# Sensor.net
KiCad netlist of a schematic drawn in Altium Designer
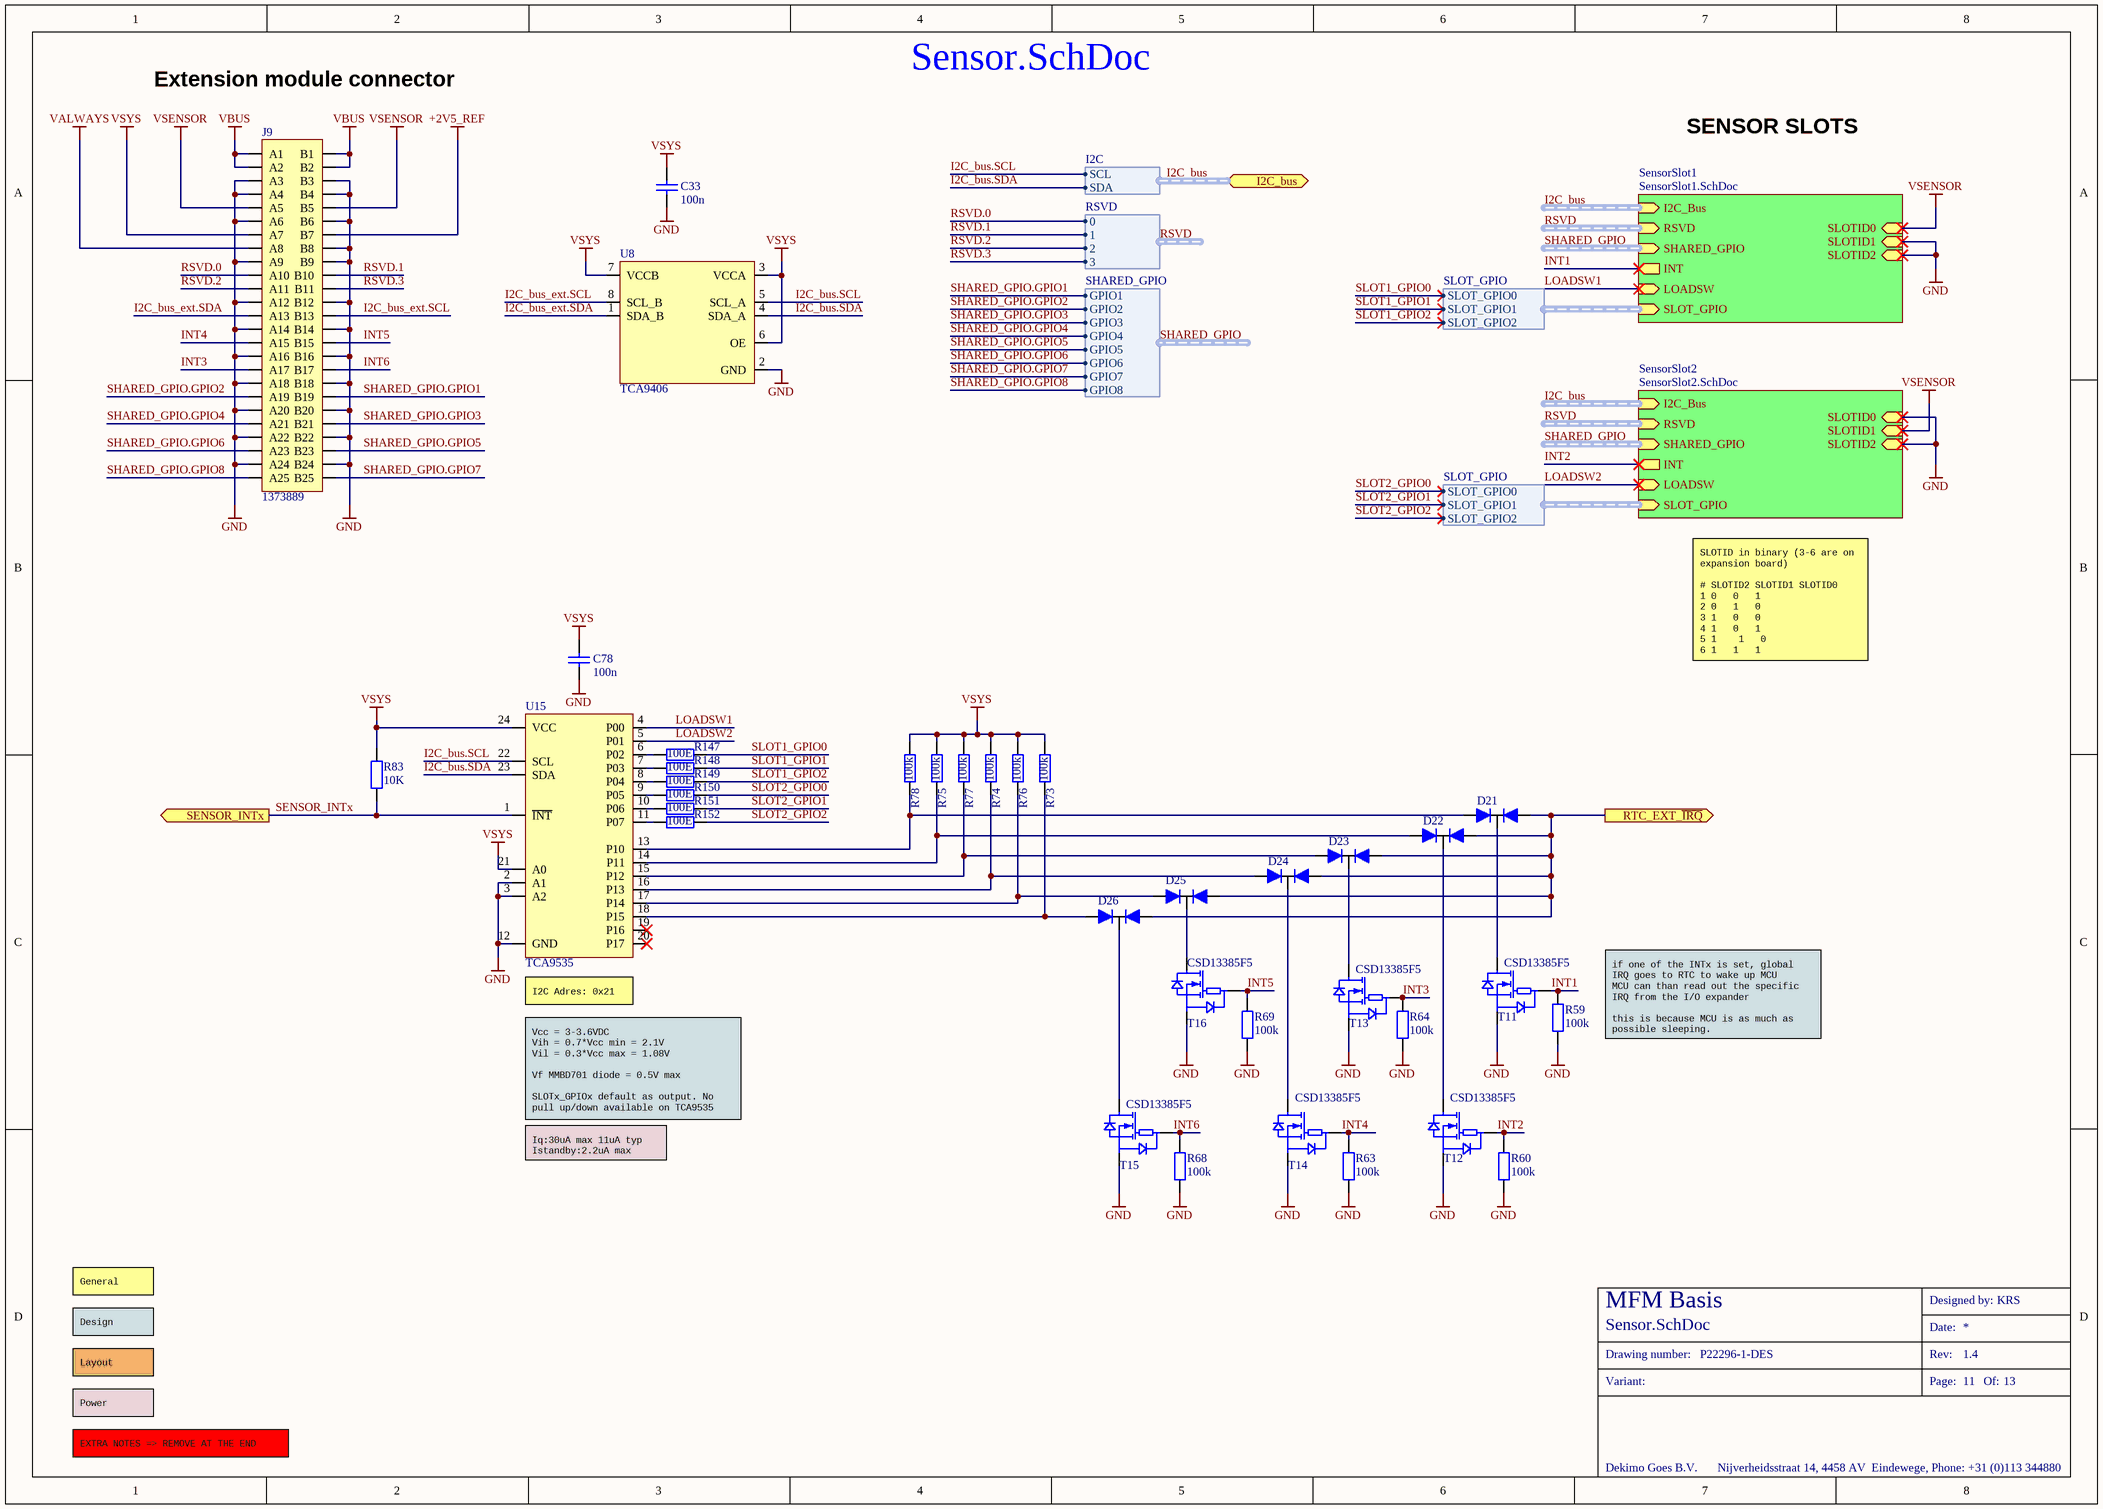
[diagram p0: Sensor.SchDoc]

(export (version "E")
  (design (tool "Eeschema 10.0.6"))
  (components
    (comp (ref "C33")
      (value "100n")
      (footprint "CAPC1608X09N")
      (description "100nF 50V 10% X7R")
      (libsource (lib "DCI") (part "Capacitor_NP"))
    )
    (comp (ref "C78")
      (value "100n")
      (footprint "CAPC1608X09N")
      (description "100nF 50V 10% X7R")
      (libsource (lib "DCI") (part "Capacitor_NP"))
    )
    (comp (ref "D21")
      (value "DIO RB508FM-40C")
      (footprint "SOT-650G001-003")
      (description "RB508, 40V, 80mA 2 com cat dio")
      (libsource (lib "DCI") (part "Diode_CC"))
    )
    (comp (ref "D22")
      (value "DIO RB508FM-40C")
      (footprint "SOT-650G001-003")
      (description "RB508, 40V, 80mA 2 com cat dio")
      (libsource (lib "DCI") (part "Diode_CC"))
    )
    (comp (ref "D23")
      (value "DIO RB508FM-40C")
      (footprint "SOT-650G001-003")
      (description "RB508, 40V, 80mA 2 com cat dio")
      (libsource (lib "DCI") (part "Diode_CC"))
    )
    (comp (ref "D24")
      (value "DIO RB508FM-40C")
      (footprint "SOT-650G001-003")
      (description "RB508, 40V, 80mA 2 com cat dio")
      (libsource (lib "DCI") (part "Diode_CC"))
    )
    (comp (ref "D25")
      (value "DIO RB508FM-40C")
      (footprint "SOT-650G001-003")
      (description "RB508, 40V, 80mA 2 com cat dio")
      (libsource (lib "DCI") (part "Diode_CC"))
    )
    (comp (ref "D26")
      (value "DIO RB508FM-40C")
      (footprint "SOT-650G001-003")
      (description "RB508, 40V, 80mA 2 com cat dio")
      (libsource (lib "DCI") (part "Diode_CC"))
    )
    (comp (ref "J9")
      (value "1373889")
      (footprint "CON-111G003-050")
      (description "2x25p socket 1.27mm straight")
      (libsource (lib "DCI") (part "2X25PIN"))
    )
    (comp (ref "R59")
      (value "100k")
      (footprint "RESC1005X04N")
      (description "100K, 62.5mW, 1%")
      (libsource (lib "DCI") (part "Resistor"))
    )
    (comp (ref "R60")
      (value "100k")
      (footprint "RESC1005X04N")
      (description "100K, 62.5mW, 1%")
      (libsource (lib "DCI") (part "Resistor"))
    )
    (comp (ref "R63")
      (value "100k")
      (footprint "RESC1005X04N")
      (description "100K, 62.5mW, 1%")
      (libsource (lib "DCI") (part "Resistor"))
    )
    (comp (ref "R64")
      (value "100k")
      (footprint "RESC1005X04N")
      (description "100K, 62.5mW, 1%")
      (libsource (lib "DCI") (part "Resistor"))
    )
    (comp (ref "R68")
      (value "100k")
      (footprint "RESC1005X04N")
      (description "100K, 62.5mW, 1%")
      (libsource (lib "DCI") (part "Resistor"))
    )
    (comp (ref "R69")
      (value "100k")
      (footprint "RESC1005X04N")
      (description "100K, 62.5mW, 1%")
      (libsource (lib "DCI") (part "Resistor"))
    )
    (comp (ref "R73")
      (value "100k")
      (footprint "RESC1005X04N")
      (description "100K, 62.5mW, 1%")
      (libsource (lib "DCI") (part "Resistor"))
    )
    (comp (ref "R74")
      (value "100k")
      (footprint "RESC1005X04N")
      (description "100K, 62.5mW, 1%")
      (libsource (lib "DCI") (part "Resistor"))
    )
    (comp (ref "R75")
      (value "100k")
      (footprint "RESC1005X04N")
      (description "100K, 62.5mW, 1%")
      (libsource (lib "DCI") (part "Resistor"))
    )
    (comp (ref "R76")
      (value "100k")
      (footprint "RESC1005X04N")
      (description "100K, 62.5mW, 1%")
      (libsource (lib "DCI") (part "Resistor"))
    )
    (comp (ref "R77")
      (value "100k")
      (footprint "RESC1005X04N")
      (description "100K, 62.5mW, 1%")
      (libsource (lib "DCI") (part "Resistor"))
    )
    (comp (ref "R78")
      (value "100k")
      (footprint "RESC1005X04N")
      (description "100K, 62.5mW, 1%")
      (libsource (lib "DCI") (part "Resistor"))
    )
    (comp (ref "R83")
      (value "10K")
      (footprint "RESC1608X13N")
      (description "10k 100mW, 1%")
      (libsource (lib "DCI") (part "Resistor"))
    )
    (comp (ref "R147")
      (value "100E")
      (footprint "RESC1608X13N")
      (description "100E 100mW, 1%")
      (libsource (lib "") (part "Resistor_1"))
    )
    (comp (ref "R148")
      (value "100E")
      (footprint "RESC1608X13N")
      (description "100E 100mW, 1%")
      (libsource (lib "") (part "Resistor_1"))
    )
    (comp (ref "R149")
      (value "100E")
      (footprint "RESC1608X13N")
      (description "100E 100mW, 1%")
      (libsource (lib "") (part "Resistor_1"))
    )
    (comp (ref "R150")
      (value "100E")
      (footprint "RESC1608X13N")
      (description "100E 100mW, 1%")
      (libsource (lib "") (part "Resistor_1"))
    )
    (comp (ref "R151")
      (value "100E")
      (footprint "RESC1608X13N")
      (description "100E 100mW, 1%")
      (libsource (lib "") (part "Resistor_1"))
    )
    (comp (ref "R152")
      (value "100E")
      (footprint "RESC1608X13N")
      (description "100E 100mW, 1%")
      (libsource (lib "") (part "Resistor_1"))
    )
    (comp (ref "T11")
      (value "CSD13385F5")
      (footprint "DFN-500G000-003")
      (description "7.1A, 12V, N-channel FemtoFet")
      (libsource (lib "DCI") (part "MOSFET_CSD13385F5"))
    )
    (comp (ref "T12")
      (value "CSD13385F5")
      (footprint "DFN-500G000-003")
      (description "7.1A, 12V, N-channel FemtoFet")
      (libsource (lib "DCI") (part "MOSFET_CSD13385F5"))
    )
    (comp (ref "T13")
      (value "CSD13385F5")
      (footprint "DFN-500G000-003")
      (description "7.1A, 12V, N-channel FemtoFet")
      (libsource (lib "DCI") (part "MOSFET_CSD13385F5"))
    )
    (comp (ref "T14")
      (value "CSD13385F5")
      (footprint "DFN-500G000-003")
      (description "7.1A, 12V, N-channel FemtoFet")
      (libsource (lib "DCI") (part "MOSFET_CSD13385F5"))
    )
    (comp (ref "T15")
      (value "CSD13385F5")
      (footprint "DFN-500G000-003")
      (description "7.1A, 12V, N-channel FemtoFet")
      (libsource (lib "DCI") (part "MOSFET_CSD13385F5"))
    )
    (comp (ref "T16")
      (value "CSD13385F5")
      (footprint "DFN-500G000-003")
      (description "7.1A, 12V, N-channel FemtoFet")
      (libsource (lib "DCI") (part "MOSFET_CSD13385F5"))
    )
    (comp (ref "U8")
      (value "TCA9406")
      (footprint "SOP-650002-008")
      (description "I2C Level translator")
      (libsource (lib "DCI") (part "LVLSHIFT_I2C_TCA9406_SM8"))
    )
    (comp (ref "U15")
      (value "TCA9535")
      (footprint "SOP-650001-024")
      (description "16-bits  I2C I/O Expander")
      (libsource (lib "DCI") (part "IO_EXPANDER_TCA9535"))
    )
  )
  (nets
    (net (code "8") (name "+2V5_REF") (class "Default")
      (node (ref "J9") (pin "B7") (pinfunction "B7_B7") (pintype "passive"))
    )
    (net (code "9") (name "/I2C_bus.SCL") (class "Default")
      (node (ref "U15") (pin "22") (pinfunction "SCL_22") (pintype "passive"))
      (node (ref "U8") (pin "5") (pinfunction "SCL_A_5") (pintype "passive"))
    )
    (net (code "10") (name "/I2C_bus.SDA") (class "Default")
      (node (ref "U15") (pin "23") (pinfunction "SDA_23") (pintype "passive"))
      (node (ref "U8") (pin "4") (pinfunction "SDA_A_4") (pintype "passive"))
    )
    (net (code "11") (name "/I2C_bus_ext.SCL") (class "Default")
      (node (ref "J9") (pin "B13") (pinfunction "B13_B13") (pintype "passive"))
      (node (ref "U8") (pin "8") (pinfunction "SCL_B_8") (pintype "passive"))
    )
    (net (code "12") (name "/I2C_bus_ext.SDA") (class "Default")
      (node (ref "J9") (pin "A13") (pinfunction "A13_A13") (pintype "passive"))
      (node (ref "U8") (pin "1") (pinfunction "SDA_B_1") (pintype "passive"))
    )
    (net (code "14") (name "/INT1") (class "Default")
      (node (ref "R59") (pin "2") (pinfunction "2_2") (pintype "passive"))
      (node (ref "T11") (pin "G") (pinfunction "G_G") (pintype "passive"))
    )
    (net (code "15") (name "/INT2") (class "Default")
      (node (ref "R60") (pin "2") (pinfunction "2_2") (pintype "passive"))
      (node (ref "T12") (pin "G") (pinfunction "G_G") (pintype "passive"))
    )
    (net (code "16") (name "/INT3") (class "Default")
      (node (ref "J9") (pin "A17") (pinfunction "A17_A17") (pintype "passive"))
      (node (ref "R64") (pin "2") (pinfunction "2_2") (pintype "passive"))
      (node (ref "T13") (pin "G") (pinfunction "G_G") (pintype "passive"))
    )
    (net (code "17") (name "/INT4") (class "Default")
      (node (ref "J9") (pin "A15") (pinfunction "A15_A15") (pintype "passive"))
      (node (ref "R63") (pin "2") (pinfunction "2_2") (pintype "passive"))
      (node (ref "T14") (pin "G") (pinfunction "G_G") (pintype "passive"))
    )
    (net (code "18") (name "/INT5") (class "Default")
      (node (ref "J9") (pin "B15") (pinfunction "B15_B15") (pintype "passive"))
      (node (ref "R69") (pin "2") (pinfunction "2_2") (pintype "passive"))
      (node (ref "T16") (pin "G") (pinfunction "G_G") (pintype "passive"))
    )
    (net (code "19") (name "/INT6") (class "Default")
      (node (ref "J9") (pin "B17") (pinfunction "B17_B17") (pintype "passive"))
      (node (ref "R68") (pin "2") (pinfunction "2_2") (pintype "passive"))
      (node (ref "T15") (pin "G") (pinfunction "G_G") (pintype "passive"))
    )
    (net (code "20") (name "/LOADSW1") (class "Default")
      (node (ref "U15") (pin "4") (pinfunction "P00_4") (pintype "passive"))
    )
    (net (code "21") (name "/LOADSW2") (class "Default")
      (node (ref "U15") (pin "5") (pinfunction "P01_5") (pintype "passive"))
    )
    (net (code "22") (name "/RSVD.0") (class "Default")
      (node (ref "J9") (pin "A10") (pinfunction "A10_A10") (pintype "passive"))
    )
    (net (code "23") (name "/RSVD.1") (class "Default")
      (node (ref "J9") (pin "B10") (pinfunction "B10_B10") (pintype "passive"))
    )
    (net (code "24") (name "/RSVD.2") (class "Default")
      (node (ref "J9") (pin "A11") (pinfunction "A11_A11") (pintype "passive"))
    )
    (net (code "25") (name "/RSVD.3") (class "Default")
      (node (ref "J9") (pin "B11") (pinfunction "B11_B11") (pintype "passive"))
    )
    (net (code "27") (name "/RTC_EXT_~{IRQ}") (class "Default")
      (node (ref "D21") (pin "A2") (pinfunction "A2_A2") (pintype "passive"))
      (node (ref "D22") (pin "A2") (pinfunction "A2_A2") (pintype "passive"))
      (node (ref "D23") (pin "A2") (pinfunction "A2_A2") (pintype "passive"))
      (node (ref "D24") (pin "A2") (pinfunction "A2_A2") (pintype "passive"))
      (node (ref "D25") (pin "A2") (pinfunction "A2_A2") (pintype "passive"))
      (node (ref "D26") (pin "A2") (pinfunction "A2_A2") (pintype "passive"))
    )
    (net (code "28") (name "/SENSOR_INTx") (class "Default")
      (node (ref "R83") (pin "1") (pinfunction "1_1") (pintype "passive"))
      (node (ref "U15") (pin "1") (pinfunction "~{INT}_1") (pintype "passive"))
    )
    (net (code "29") (name "/SHARED_GPIO.GPIO1") (class "Default")
      (node (ref "J9") (pin "B19") (pinfunction "B19_B19") (pintype "passive"))
    )
    (net (code "30") (name "/SHARED_GPIO.GPIO2") (class "Default")
      (node (ref "J9") (pin "A19") (pinfunction "A19_A19") (pintype "passive"))
    )
    (net (code "31") (name "/SHARED_GPIO.GPIO3") (class "Default")
      (node (ref "J9") (pin "B21") (pinfunction "B21_B21") (pintype "passive"))
    )
    (net (code "32") (name "/SHARED_GPIO.GPIO4") (class "Default")
      (node (ref "J9") (pin "A21") (pinfunction "A21_A21") (pintype "passive"))
    )
    (net (code "33") (name "/SHARED_GPIO.GPIO5") (class "Default")
      (node (ref "J9") (pin "B23") (pinfunction "B23_B23") (pintype "passive"))
    )
    (net (code "34") (name "/SHARED_GPIO.GPIO6") (class "Default")
      (node (ref "J9") (pin "A23") (pinfunction "A23_A23") (pintype "passive"))
    )
    (net (code "35") (name "/SHARED_GPIO.GPIO7") (class "Default")
      (node (ref "J9") (pin "B25") (pinfunction "B25_B25") (pintype "passive"))
    )
    (net (code "36") (name "/SHARED_GPIO.GPIO8") (class "Default")
      (node (ref "J9") (pin "A25") (pinfunction "A25_A25") (pintype "passive"))
    )
    (net (code "38") (name "/SLOT1_GPIO0") (class "Default")
      (node (ref "R147") (pin "2") (pinfunction "2_2") (pintype "passive"))
    )
    (net (code "39") (name "/SLOT1_GPIO1") (class "Default")
      (node (ref "R148") (pin "2") (pinfunction "2_2") (pintype "passive"))
    )
    (net (code "40") (name "/SLOT1_GPIO2") (class "Default")
      (node (ref "R149") (pin "2") (pinfunction "2_2") (pintype "passive"))
    )
    (net (code "41") (name "/SLOT2_GPIO0") (class "Default")
      (node (ref "R150") (pin "2") (pinfunction "2_2") (pintype "passive"))
    )
    (net (code "42") (name "/SLOT2_GPIO1") (class "Default")
      (node (ref "R151") (pin "2") (pinfunction "2_2") (pintype "passive"))
    )
    (net (code "43") (name "/SLOT2_GPIO2") (class "Default")
      (node (ref "R152") (pin "2") (pinfunction "2_2") (pintype "passive"))
    )
    (net (code "48") (name "GND") (class "Default")
      (node (ref "C33") (pin "1") (pinfunction "1_1") (pintype "passive"))
      (node (ref "C78") (pin "1") (pinfunction "1_1") (pintype "passive"))
      (node (ref "J9") (pin "A12") (pinfunction "A12_A12") (pintype "passive"))
      (node (ref "J9") (pin "A14") (pinfunction "A14_A14") (pintype "passive"))
      (node (ref "J9") (pin "A16") (pinfunction "A16_A16") (pintype "passive"))
      (node (ref "J9") (pin "A18") (pinfunction "A18_A18") (pintype "passive"))
      (node (ref "J9") (pin "A20") (pinfunction "A20_A20") (pintype "passive"))
      (node (ref "J9") (pin "A22") (pinfunction "A22_A22") (pintype "passive"))
      (node (ref "J9") (pin "A24") (pinfunction "A24_A24") (pintype "passive"))
      (node (ref "J9") (pin "A3") (pinfunction "A3_A3") (pintype "passive"))
      (node (ref "J9") (pin "A4") (pinfunction "A4_A4") (pintype "passive"))
      (node (ref "J9") (pin "A6") (pinfunction "A6_A6") (pintype "passive"))
      (node (ref "J9") (pin "A9") (pinfunction "A9_A9") (pintype "passive"))
      (node (ref "J9") (pin "B12") (pinfunction "B12_B12") (pintype "passive"))
      (node (ref "J9") (pin "B14") (pinfunction "B14_B14") (pintype "passive"))
      (node (ref "J9") (pin "B16") (pinfunction "B16_B16") (pintype "passive"))
      (node (ref "J9") (pin "B18") (pinfunction "B18_B18") (pintype "passive"))
      (node (ref "J9") (pin "B20") (pinfunction "B20_B20") (pintype "passive"))
      (node (ref "J9") (pin "B22") (pinfunction "B22_B22") (pintype "passive"))
      (node (ref "J9") (pin "B24") (pinfunction "B24_B24") (pintype "passive"))
      (node (ref "J9") (pin "B3") (pinfunction "B3_B3") (pintype "passive"))
      (node (ref "J9") (pin "B4") (pinfunction "B4_B4") (pintype "passive"))
      (node (ref "J9") (pin "B6") (pinfunction "B6_B6") (pintype "passive"))
      (node (ref "J9") (pin "B8") (pinfunction "B8_B8") (pintype "passive"))
      (node (ref "J9") (pin "B9") (pinfunction "B9_B9") (pintype "passive"))
      (node (ref "R59") (pin "1") (pinfunction "1_1") (pintype "passive"))
      (node (ref "R60") (pin "1") (pinfunction "1_1") (pintype "passive"))
      (node (ref "R63") (pin "1") (pinfunction "1_1") (pintype "passive"))
      (node (ref "R64") (pin "1") (pinfunction "1_1") (pintype "passive"))
      (node (ref "R68") (pin "1") (pinfunction "1_1") (pintype "passive"))
      (node (ref "R69") (pin "1") (pinfunction "1_1") (pintype "passive"))
      (node (ref "T11") (pin "S") (pinfunction "S_S") (pintype "passive"))
      (node (ref "T12") (pin "S") (pinfunction "S_S") (pintype "passive"))
      (node (ref "T13") (pin "S") (pinfunction "S_S") (pintype "passive"))
      (node (ref "T14") (pin "S") (pinfunction "S_S") (pintype "passive"))
      (node (ref "T15") (pin "S") (pinfunction "S_S") (pintype "passive"))
      (node (ref "T16") (pin "S") (pinfunction "S_S") (pintype "passive"))
      (node (ref "U15") (pin "12") (pinfunction "GND_12") (pintype "passive"))
      (node (ref "U15") (pin "2") (pinfunction "A1_2") (pintype "passive"))
      (node (ref "U15") (pin "3") (pinfunction "A2_3") (pintype "passive"))
      (node (ref "U8") (pin "2") (pinfunction "GND_2") (pintype "power_in"))
    )
    (net (code "49") (name "Net-(D21-PadC)") (class "Default")
      (node (ref "D21") (pin "C") (pinfunction "C_C") (pintype "passive"))
      (node (ref "T11") (pin "D") (pinfunction "D_D") (pintype "passive"))
    )
    (net (code "50") (name "Net-(D22-PadC)") (class "Default")
      (node (ref "D22") (pin "C") (pinfunction "C_C") (pintype "passive"))
      (node (ref "T12") (pin "D") (pinfunction "D_D") (pintype "passive"))
    )
    (net (code "51") (name "Net-(D23-PadC)") (class "Default")
      (node (ref "D23") (pin "C") (pinfunction "C_C") (pintype "passive"))
      (node (ref "T13") (pin "D") (pinfunction "D_D") (pintype "passive"))
    )
    (net (code "52") (name "Net-(D24-PadC)") (class "Default")
      (node (ref "D24") (pin "C") (pinfunction "C_C") (pintype "passive"))
      (node (ref "T14") (pin "D") (pinfunction "D_D") (pintype "passive"))
    )
    (net (code "53") (name "Net-(D25-PadC)") (class "Default")
      (node (ref "D25") (pin "C") (pinfunction "C_C") (pintype "passive"))
      (node (ref "T16") (pin "D") (pinfunction "D_D") (pintype "passive"))
    )
    (net (code "54") (name "Net-(D26-PadC)") (class "Default")
      (node (ref "D26") (pin "C") (pinfunction "C_C") (pintype "passive"))
      (node (ref "T15") (pin "D") (pinfunction "D_D") (pintype "passive"))
    )
    (net (code "55") (name "Net-(U15-P02)") (class "Default")
      (node (ref "R147") (pin "1") (pinfunction "1_1") (pintype "passive"))
      (node (ref "U15") (pin "6") (pinfunction "P02_6") (pintype "passive"))
    )
    (net (code "56") (name "Net-(U15-P03)") (class "Default")
      (node (ref "R148") (pin "1") (pinfunction "1_1") (pintype "passive"))
      (node (ref "U15") (pin "7") (pinfunction "P03_7") (pintype "passive"))
    )
    (net (code "57") (name "Net-(U15-P04)") (class "Default")
      (node (ref "R149") (pin "1") (pinfunction "1_1") (pintype "passive"))
      (node (ref "U15") (pin "8") (pinfunction "P04_8") (pintype "passive"))
    )
    (net (code "58") (name "Net-(U15-P05)") (class "Default")
      (node (ref "R150") (pin "1") (pinfunction "1_1") (pintype "passive"))
      (node (ref "U15") (pin "9") (pinfunction "P05_9") (pintype "passive"))
    )
    (net (code "59") (name "Net-(U15-P06)") (class "Default")
      (node (ref "R151") (pin "1") (pinfunction "1_1") (pintype "passive"))
      (node (ref "U15") (pin "10") (pinfunction "P06_10") (pintype "passive"))
    )
    (net (code "60") (name "Net-(U15-P07)") (class "Default")
      (node (ref "R152") (pin "1") (pinfunction "1_1") (pintype "passive"))
      (node (ref "U15") (pin "11") (pinfunction "P07_11") (pintype "passive"))
    )
    (net (code "61") (name "Net-(U15-P10)") (class "Default")
      (node (ref "D21") (pin "A1") (pinfunction "A1_A1") (pintype "passive"))
      (node (ref "R78") (pin "1") (pinfunction "1_1") (pintype "passive"))
      (node (ref "U15") (pin "13") (pinfunction "P10_13") (pintype "passive"))
    )
    (net (code "62") (name "Net-(U15-P11)") (class "Default")
      (node (ref "D22") (pin "A1") (pinfunction "A1_A1") (pintype "passive"))
      (node (ref "R75") (pin "1") (pinfunction "1_1") (pintype "passive"))
      (node (ref "U15") (pin "14") (pinfunction "P11_14") (pintype "passive"))
    )
    (net (code "63") (name "Net-(U15-P12)") (class "Default")
      (node (ref "D23") (pin "A1") (pinfunction "A1_A1") (pintype "passive"))
      (node (ref "R77") (pin "1") (pinfunction "1_1") (pintype "passive"))
      (node (ref "U15") (pin "15") (pinfunction "P12_15") (pintype "passive"))
    )
    (net (code "64") (name "Net-(U15-P13)") (class "Default")
      (node (ref "D24") (pin "A1") (pinfunction "A1_A1") (pintype "passive"))
      (node (ref "R74") (pin "1") (pinfunction "1_1") (pintype "passive"))
      (node (ref "U15") (pin "16") (pinfunction "P13_16") (pintype "passive"))
    )
    (net (code "65") (name "Net-(U15-P14)") (class "Default")
      (node (ref "D25") (pin "A1") (pinfunction "A1_A1") (pintype "passive"))
      (node (ref "R76") (pin "1") (pinfunction "1_1") (pintype "passive"))
      (node (ref "U15") (pin "17") (pinfunction "P14_17") (pintype "passive"))
    )
    (net (code "66") (name "Net-(U15-P15)") (class "Default")
      (node (ref "D26") (pin "A1") (pinfunction "A1_A1") (pintype "passive"))
      (node (ref "R73") (pin "1") (pinfunction "1_1") (pintype "passive"))
      (node (ref "U15") (pin "18") (pinfunction "P15_18") (pintype "passive"))
    )
    (net (code "67") (name "VALWAYS") (class "Default")
      (node (ref "J9") (pin "A8") (pinfunction "A8_A8") (pintype "passive"))
    )
    (net (code "68") (name "VBUS") (class "Default")
      (node (ref "J9") (pin "A1") (pinfunction "A1_A1") (pintype "passive"))
      (node (ref "J9") (pin "A2") (pinfunction "A2_A2") (pintype "passive"))
      (node (ref "J9") (pin "B1") (pinfunction "B1_B1") (pintype "passive"))
      (node (ref "J9") (pin "B2") (pinfunction "B2_B2") (pintype "passive"))
    )
    (net (code "69") (name "VSENSOR") (class "Default")
      (node (ref "J9") (pin "A5") (pinfunction "A5_A5") (pintype "passive"))
      (node (ref "J9") (pin "B5") (pinfunction "B5_B5") (pintype "passive"))
    )
    (net (code "70") (name "VSYS") (class "Default")
      (node (ref "C33") (pin "2") (pinfunction "2_2") (pintype "passive"))
      (node (ref "C78") (pin "2") (pinfunction "2_2") (pintype "passive"))
      (node (ref "J9") (pin "A7") (pinfunction "A7_A7") (pintype "passive"))
      (node (ref "R73") (pin "2") (pinfunction "2_2") (pintype "passive"))
      (node (ref "R74") (pin "2") (pinfunction "2_2") (pintype "passive"))
      (node (ref "R75") (pin "2") (pinfunction "2_2") (pintype "passive"))
      (node (ref "R76") (pin "2") (pinfunction "2_2") (pintype "passive"))
      (node (ref "R77") (pin "2") (pinfunction "2_2") (pintype "passive"))
      (node (ref "R78") (pin "2") (pinfunction "2_2") (pintype "passive"))
      (node (ref "R83") (pin "2") (pinfunction "2_2") (pintype "passive"))
      (node (ref "U15") (pin "21") (pinfunction "A0_21") (pintype "passive"))
      (node (ref "U15") (pin "24") (pinfunction "VCC_24") (pintype "passive"))
      (node (ref "U8") (pin "3") (pinfunction "VCCA_3") (pintype "power_in"))
      (node (ref "U8") (pin "6") (pinfunction "OE_6") (pintype "passive"))
      (node (ref "U8") (pin "7") (pinfunction "VCCB_7") (pintype "power_in"))
    )
    (net (code "71") (name "unconnected-(U15-P16-Pad19)") (class "Default")
      (node (ref "U15") (pin "19") (pinfunction "P16_19") (pintype "passive+no_connect"))
    )
    (net (code "72") (name "unconnected-(U15-P17-Pad20)") (class "Default")
      (node (ref "U15") (pin "20") (pinfunction "P17_20") (pintype "passive+no_connect"))
    )
  )
)
